# PSU_main.net
KiCad netlist of a schematic drawn in EAGLE
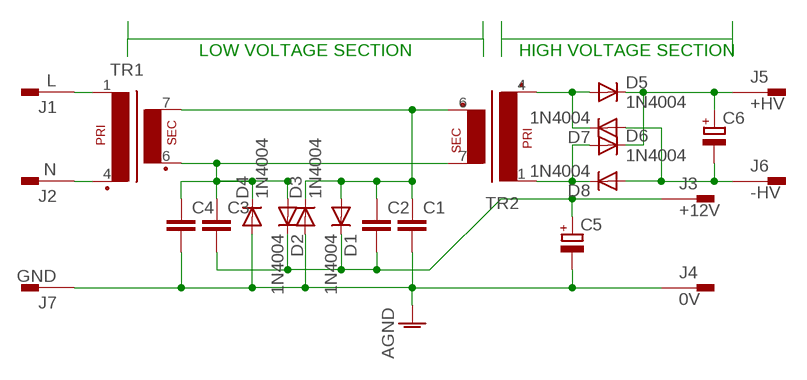
[diagram p0: schematic, sheet 1]
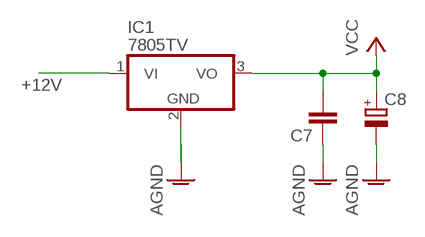
[diagram p1: schematic, sheet 2]

(export (version "E")
  (design (tool "Eeschema 10.0.6"))
  (components
    (comp (ref "C1")
      (value "C5/3")
      (footprint "eagle-import:C5B3")
      (libsource (lib "eagle-import") (part "C5/3"))
    )
    (comp (ref "C2")
      (value "C5/3")
      (footprint "eagle-import:C5B3")
      (libsource (lib "eagle-import") (part "C5/3"))
    )
    (comp (ref "C3")
      (value "C5/3")
      (footprint "eagle-import:C5B3")
      (libsource (lib "eagle-import") (part "C5/3"))
    )
    (comp (ref "C4")
      (value "C5/3")
      (footprint "eagle-import:C5B3")
      (libsource (lib "eagle-import") (part "C5/3"))
    )
    (comp (ref "C5")
      (value "CPOL-EUE10-20")
      (footprint "eagle-import:EB20D")
      (libsource (lib "eagle-import") (part "CPOL-EUE10-20"))
    )
    (comp (ref "C6")
      (value "CPOL-EUE10-20")
      (footprint "eagle-import:EB20D")
      (libsource (lib "eagle-import") (part "CPOL-EUE10-20"))
    )
    (comp (ref "D1")
      (value "1N4004")
      (footprint "eagle-import:DO41-10")
      (libsource (lib "eagle-import") (part "1N4004"))
    )
    (comp (ref "D2")
      (value "1N4004")
      (footprint "eagle-import:DO41-10")
      (libsource (lib "eagle-import") (part "1N4004"))
    )
    (comp (ref "D3")
      (value "1N4004")
      (footprint "eagle-import:DO41-10")
      (libsource (lib "eagle-import") (part "1N4004"))
    )
    (comp (ref "D4")
      (value "1N4004")
      (footprint "eagle-import:DO41-10")
      (libsource (lib "eagle-import") (part "1N4004"))
    )
    (comp (ref "D5")
      (value "1N4004")
      (footprint "eagle-import:DO41-10")
      (libsource (lib "eagle-import") (part "1N4004"))
    )
    (comp (ref "D6")
      (value "1N4004")
      (footprint "eagle-import:DO41-10")
      (libsource (lib "eagle-import") (part "1N4004"))
    )
    (comp (ref "D7")
      (value "1N4004")
      (footprint "eagle-import:DO41-10")
      (libsource (lib "eagle-import") (part "1N4004"))
    )
    (comp (ref "D8")
      (value "1N4004")
      (footprint "eagle-import:DO41-10")
      (libsource (lib "eagle-import") (part "1N4004"))
    )
    (comp (ref "J1")
      (value "L")
      (footprint "eagle-import:62221")
      (fields (field (name "MF") "TYCO ELECTRONICS") (field (name "MPN") "62221-1"))
      (libsource (lib "eagle-import") (part "PIN1-2"))
    )
    (comp (ref "J2")
      (value "N")
      (footprint "eagle-import:62221")
      (fields (field (name "MF") "TYCO ELECTRONICS") (field (name "MPN") "62221-1"))
      (libsource (lib "eagle-import") (part "PIN1-2"))
    )
    (comp (ref "J3")
      (value "+12V")
      (footprint "eagle-import:62221")
      (fields (field (name "MF") "TYCO ELECTRONICS") (field (name "MPN") "62221-1"))
      (libsource (lib "eagle-import") (part "PIN1-2"))
    )
    (comp (ref "J4")
      (value "0V")
      (footprint "eagle-import:62221")
      (fields (field (name "MF") "TYCO ELECTRONICS") (field (name "MPN") "62221-1"))
      (libsource (lib "eagle-import") (part "PIN1-2"))
    )
    (comp (ref "J5")
      (value "+HV")
      (footprint "eagle-import:62221")
      (fields (field (name "MF") "TYCO ELECTRONICS") (field (name "MPN") "62221-1"))
      (libsource (lib "eagle-import") (part "PIN1-2"))
    )
    (comp (ref "J6")
      (value "-HV")
      (footprint "eagle-import:62221")
      (fields (field (name "MF") "TYCO ELECTRONICS") (field (name "MPN") "62221-1"))
      (libsource (lib "eagle-import") (part "PIN1-2"))
    )
    (comp (ref "J7")
      (value "GND")
      (footprint "eagle-import:62221")
      (fields (field (name "MF") "TYCO ELECTRONICS") (field (name "MPN") "62221-1"))
      (libsource (lib "eagle-import") (part "PIN1-2"))
    )
    (comp (ref "TR1")
      (value "EE20-1")
      (footprint "eagle-import:EE20-1")
      (libsource (lib "eagle-import") (part "EE20-1"))
    )
    (comp (ref "TR2")
      (value "EE20-1")
      (footprint "eagle-import:EE20-1")
      (libsource (lib "eagle-import") (part "EE20-1"))
    )
    (comp (ref "C7")
      (value "C-EU050-025X075")
      (footprint "eagle-import:C050-025X075")
      (libsource (lib "eagle-import") (part "C-EU050-025X075"))
    )
    (comp (ref "C8")
      (value "CPOL-EUE5-10.5")
      (footprint "eagle-import:E5-10,5")
      (libsource (lib "eagle-import") (part "CPOL-EUE5-10.5"))
    )
    (comp (ref "IC1")
      (value "7805TV")
      (footprint "eagle-import:TO220V")
      (libsource (lib "eagle-import") (part "78TV05"))
    )
  )
  (nets
    (net (code "1") (name "+12V") (class "Default")
      (node (ref "C2") (pin "2") (pinfunction "2_2") (pintype "passive"))
      (node (ref "C3") (pin "2") (pinfunction "2_2") (pintype "passive"))
      (node (ref "C5") (pin "+") (pinfunction "+_+") (pintype "passive"))
      (node (ref "D1") (pin "C") (pinfunction "C_C") (pintype "passive"))
      (node (ref "D2") (pin "C") (pinfunction "C_C") (pintype "passive"))
      (node (ref "IC1") (pin "1") (pinfunction "VI_1") (pintype "input"))
      (node (ref "J3") (pin "1") (pinfunction "1_1") (pintype "passive"))
    )
    (net (code "2") (name "AGND") (class "Default")
      (node (ref "C1") (pin "2") (pinfunction "2_2") (pintype "passive"))
      (node (ref "C4") (pin "2") (pinfunction "2_2") (pintype "passive"))
      (node (ref "C5") (pin "-") (pinfunction "-_-") (pintype "passive"))
      (node (ref "C7") (pin "1") (pinfunction "1_1") (pintype "passive"))
      (node (ref "C8") (pin "-") (pinfunction "-_-") (pintype "passive"))
      (node (ref "D3") (pin "A") (pinfunction "A_A") (pintype "passive"))
      (node (ref "D4") (pin "A") (pinfunction "A_A") (pintype "passive"))
      (node (ref "IC1") (pin "2") (pinfunction "GND_2") (pintype "passive"))
      (node (ref "J4") (pin "1") (pinfunction "1_1") (pintype "passive"))
      (node (ref "J7") (pin "1") (pinfunction "1_1") (pintype "passive"))
    )
    (net (code "3") (name "Net-(C6-Pad+)") (class "Default")
      (node (ref "C6") (pin "+") (pinfunction "+_+") (pintype "passive"))
      (node (ref "D5") (pin "C") (pinfunction "C_C") (pintype "passive"))
      (node (ref "D6") (pin "C") (pinfunction "C_C") (pintype "passive"))
      (node (ref "J5") (pin "1") (pinfunction "1_1") (pintype "passive"))
    )
    (net (code "4") (name "Net-(C6-Pad-)") (class "Default")
      (node (ref "C6") (pin "-") (pinfunction "-_-") (pintype "passive"))
      (node (ref "D7") (pin "A") (pinfunction "A_A") (pintype "passive"))
      (node (ref "D8") (pin "A") (pinfunction "A_A") (pintype "passive"))
      (node (ref "J6") (pin "1") (pinfunction "1_1") (pintype "passive"))
    )
    (net (code "5") (name "Net-(TR1-P1)") (class "Default")
      (node (ref "J1") (pin "1") (pinfunction "1_1") (pintype "passive"))
      (node (ref "TR1") (pin "1") (pinfunction "P1_1") (pintype "passive"))
    )
    (net (code "6") (name "Net-(TR1-P2)") (class "Default")
      (node (ref "J2") (pin "1") (pinfunction "1_1") (pintype "passive"))
      (node (ref "TR1") (pin "4") (pinfunction "P2_4") (pintype "passive"))
    )
    (net (code "7") (name "Net-(TR1-S3)") (class "Default")
      (node (ref "C3") (pin "1") (pinfunction "1_1") (pintype "passive"))
      (node (ref "C4") (pin "1") (pinfunction "1_1") (pintype "passive"))
      (node (ref "D2") (pin "A") (pinfunction "A_A") (pintype "passive"))
      (node (ref "D4") (pin "C") (pinfunction "C_C") (pintype "passive"))
      (node (ref "TR1") (pin "6") (pinfunction "S3_6") (pintype "passive"))
      (node (ref "TR2") (pin "7") (pinfunction "S4_7") (pintype "passive"))
    )
    (net (code "8") (name "Net-(TR1-S4)") (class "Default")
      (node (ref "C1") (pin "1") (pinfunction "1_1") (pintype "passive"))
      (node (ref "C2") (pin "1") (pinfunction "1_1") (pintype "passive"))
      (node (ref "D1") (pin "A") (pinfunction "A_A") (pintype "passive"))
      (node (ref "D3") (pin "C") (pinfunction "C_C") (pintype "passive"))
      (node (ref "TR1") (pin "7") (pinfunction "S4_7") (pintype "passive"))
      (node (ref "TR2") (pin "6") (pinfunction "S3_6") (pintype "passive"))
    )
    (net (code "9") (name "Net-(TR2-P1)") (class "Default")
      (node (ref "D6") (pin "A") (pinfunction "A_A") (pintype "passive"))
      (node (ref "D8") (pin "C") (pinfunction "C_C") (pintype "passive"))
      (node (ref "TR2") (pin "1") (pinfunction "P1_1") (pintype "passive"))
    )
    (net (code "10") (name "Net-(TR2-P2)") (class "Default")
      (node (ref "D5") (pin "A") (pinfunction "A_A") (pintype "passive"))
      (node (ref "D7") (pin "C") (pinfunction "C_C") (pintype "passive"))
      (node (ref "TR2") (pin "4") (pinfunction "P2_4") (pintype "passive"))
    )
    (net (code "11") (name "VCC") (class "Default")
      (node (ref "C7") (pin "2") (pinfunction "2_2") (pintype "passive"))
      (node (ref "C8") (pin "+") (pinfunction "+_+") (pintype "passive"))
      (node (ref "IC1") (pin "3") (pinfunction "VO_3") (pintype "passive"))
    )
  )
)
